# nixie_test_v4.net
KiCad netlist of a schematic drawn in EAGLE
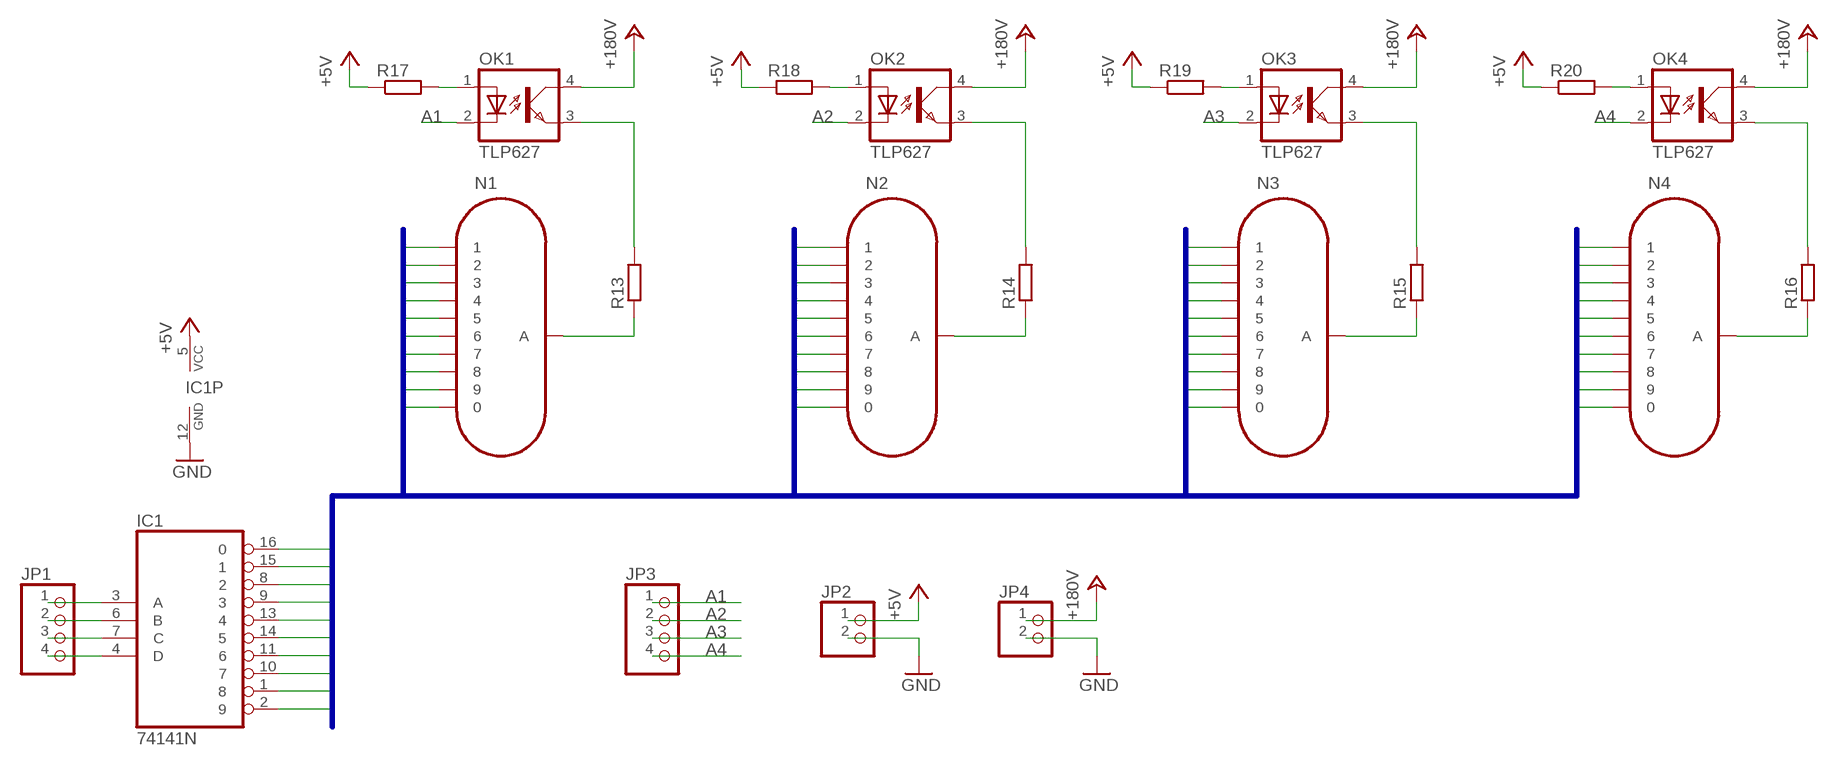
[diagram p0: schematic, sheet 1]

(export (version "E")
  (design (tool "Eeschema 10.0.6"))
  (components
    (comp (ref "IC1")
      (value "74141N")
      (footprint "eagle-import:DIL16")
      (libsource (lib "eagle-import") (part "74141N"))
    )
    (comp (ref "JP1")
      (value "PINHD-1X4")
      (footprint "eagle-import:1X04")
      (libsource (lib "eagle-import") (part "PINHD-1X4"))
    )
    (comp (ref "JP2")
      (value "PINHD-1X2")
      (footprint "eagle-import:1X02")
      (libsource (lib "eagle-import") (part "PINHD-1X2"))
    )
    (comp (ref "JP3")
      (value "PINHD-1X4")
      (footprint "eagle-import:1X04")
      (libsource (lib "eagle-import") (part "PINHD-1X4"))
    )
    (comp (ref "JP4")
      (value "PINHD-1X2")
      (footprint "eagle-import:1X02")
      (libsource (lib "eagle-import") (part "PINHD-1X2"))
    )
    (comp (ref "N1")
      (value "IN-17")
      (footprint "eagle-import:IN-17")
      (libsource (lib "eagle-import") (part "IN-17"))
    )
    (comp (ref "N2")
      (value "IN-17")
      (footprint "eagle-import:IN-17")
      (libsource (lib "eagle-import") (part "IN-17"))
    )
    (comp (ref "N3")
      (value "IN-17")
      (footprint "eagle-import:IN-17")
      (libsource (lib "eagle-import") (part "IN-17"))
    )
    (comp (ref "N4")
      (value "IN-17")
      (footprint "eagle-import:IN-17")
      (libsource (lib "eagle-import") (part "IN-17"))
    )
    (comp (ref "OK1")
      (value "TLP627")
      (footprint "eagle-import:4-SMD")
      (libsource (lib "eagle-import") (part "TLP627"))
    )
    (comp (ref "OK2")
      (value "TLP627")
      (footprint "eagle-import:4-SMD")
      (libsource (lib "eagle-import") (part "TLP627"))
    )
    (comp (ref "OK3")
      (value "TLP627")
      (footprint "eagle-import:4-SMD")
      (libsource (lib "eagle-import") (part "TLP627"))
    )
    (comp (ref "OK4")
      (value "TLP627")
      (footprint "eagle-import:4-SMD")
      (libsource (lib "eagle-import") (part "TLP627"))
    )
    (comp (ref "R13")
      (value "R-EU_10")
      (footprint "eagle-import:0207_10")
      (libsource (lib "eagle-import") (part "R-EU_10"))
    )
    (comp (ref "R14")
      (value "R-EU_10")
      (footprint "eagle-import:0207_10")
      (libsource (lib "eagle-import") (part "R-EU_10"))
    )
    (comp (ref "R15")
      (value "R-EU_10")
      (footprint "eagle-import:0207_10")
      (libsource (lib "eagle-import") (part "R-EU_10"))
    )
    (comp (ref "R16")
      (value "R-EU_10")
      (footprint "eagle-import:0207_10")
      (libsource (lib "eagle-import") (part "R-EU_10"))
    )
    (comp (ref "R17")
      (value "R-EU_R0805")
      (footprint "eagle-import:R0805")
      (libsource (lib "eagle-import") (part "R-EU_R0805"))
    )
    (comp (ref "R18")
      (value "R-EU_R0805")
      (footprint "eagle-import:R0805")
      (libsource (lib "eagle-import") (part "R-EU_R0805"))
    )
    (comp (ref "R19")
      (value "R-EU_R0805")
      (footprint "eagle-import:R0805")
      (libsource (lib "eagle-import") (part "R-EU_R0805"))
    )
    (comp (ref "R20")
      (value "R-EU_R0805")
      (footprint "eagle-import:R0805")
      (libsource (lib "eagle-import") (part "R-EU_R0805"))
    )
  )
  (nets
    (net (code "1") (name "+5V") (class "Default")
      (node (ref "IC1") (pin "5") (pinfunction "VCC_5") (pintype "power_in"))
      (node (ref "JP2") (pin "1") (pinfunction "1_1") (pintype "passive"))
      (node (ref "R17") (pin "1") (pinfunction "1_1") (pintype "passive"))
      (node (ref "R18") (pin "1") (pinfunction "1_1") (pintype "passive"))
      (node (ref "R19") (pin "1") (pinfunction "1_1") (pintype "passive"))
      (node (ref "R20") (pin "1") (pinfunction "1_1") (pintype "passive"))
    )
    (net (code "2") (name "+180V") (class "Default")
      (node (ref "JP4") (pin "1") (pinfunction "1_1") (pintype "passive"))
      (node (ref "OK1") (pin "4") (pinfunction "COL_4") (pintype "passive"))
      (node (ref "OK2") (pin "4") (pinfunction "COL_4") (pintype "passive"))
      (node (ref "OK3") (pin "4") (pinfunction "COL_4") (pintype "passive"))
      (node (ref "OK4") (pin "4") (pinfunction "COL_4") (pintype "passive"))
    )
    (net (code "3") (name "/A1") (class "Default")
      (node (ref "JP3") (pin "1") (pinfunction "1_1") (pintype "passive"))
      (node (ref "OK1") (pin "2") (pinfunction "C_2") (pintype "passive"))
    )
    (net (code "4") (name "/A2") (class "Default")
      (node (ref "JP3") (pin "2") (pinfunction "2_2") (pintype "passive"))
      (node (ref "OK2") (pin "2") (pinfunction "C_2") (pintype "passive"))
    )
    (net (code "5") (name "/A3") (class "Default")
      (node (ref "JP3") (pin "3") (pinfunction "3_3") (pintype "passive"))
      (node (ref "OK3") (pin "2") (pinfunction "C_2") (pintype "passive"))
    )
    (net (code "6") (name "/A4") (class "Default")
      (node (ref "JP3") (pin "4") (pinfunction "4_4") (pintype "passive"))
      (node (ref "OK4") (pin "2") (pinfunction "C_2") (pintype "passive"))
    )
    (net (code "7") (name "/C0") (class "Default")
      (node (ref "IC1") (pin "16") (pinfunction "0_16") (pintype "open_collector"))
      (node (ref "N1") (pin "0") (pinfunction "0_0") (pintype "bidirectional"))
      (node (ref "N2") (pin "0") (pinfunction "0_0") (pintype "bidirectional"))
      (node (ref "N3") (pin "0") (pinfunction "0_0") (pintype "bidirectional"))
      (node (ref "N4") (pin "0") (pinfunction "0_0") (pintype "bidirectional"))
    )
    (net (code "8") (name "/C1") (class "Default")
      (node (ref "IC1") (pin "15") (pinfunction "1_15") (pintype "open_collector"))
      (node (ref "N1") (pin "1") (pinfunction "1_1") (pintype "bidirectional"))
      (node (ref "N2") (pin "1") (pinfunction "1_1") (pintype "bidirectional"))
      (node (ref "N3") (pin "1") (pinfunction "1_1") (pintype "bidirectional"))
      (node (ref "N4") (pin "1") (pinfunction "1_1") (pintype "bidirectional"))
    )
    (net (code "9") (name "/C2") (class "Default")
      (node (ref "IC1") (pin "8") (pinfunction "2_8") (pintype "open_collector"))
      (node (ref "N1") (pin "2") (pinfunction "2_2") (pintype "bidirectional"))
      (node (ref "N2") (pin "2") (pinfunction "2_2") (pintype "bidirectional"))
      (node (ref "N3") (pin "2") (pinfunction "2_2") (pintype "bidirectional"))
      (node (ref "N4") (pin "2") (pinfunction "2_2") (pintype "bidirectional"))
    )
    (net (code "10") (name "/C3") (class "Default")
      (node (ref "IC1") (pin "9") (pinfunction "3_9") (pintype "open_collector"))
      (node (ref "N1") (pin "3") (pinfunction "3_3") (pintype "bidirectional"))
      (node (ref "N2") (pin "3") (pinfunction "3_3") (pintype "bidirectional"))
      (node (ref "N3") (pin "3") (pinfunction "3_3") (pintype "bidirectional"))
      (node (ref "N4") (pin "3") (pinfunction "3_3") (pintype "bidirectional"))
    )
    (net (code "11") (name "/C4") (class "Default")
      (node (ref "IC1") (pin "13") (pinfunction "4_13") (pintype "open_collector"))
      (node (ref "N1") (pin "4") (pinfunction "4_4") (pintype "bidirectional"))
      (node (ref "N2") (pin "4") (pinfunction "4_4") (pintype "bidirectional"))
      (node (ref "N3") (pin "4") (pinfunction "4_4") (pintype "bidirectional"))
      (node (ref "N4") (pin "4") (pinfunction "4_4") (pintype "bidirectional"))
    )
    (net (code "12") (name "/C5") (class "Default")
      (node (ref "IC1") (pin "14") (pinfunction "5_14") (pintype "open_collector"))
      (node (ref "N1") (pin "5") (pinfunction "5_5") (pintype "bidirectional"))
      (node (ref "N2") (pin "5") (pinfunction "5_5") (pintype "bidirectional"))
      (node (ref "N3") (pin "5") (pinfunction "5_5") (pintype "bidirectional"))
      (node (ref "N4") (pin "5") (pinfunction "5_5") (pintype "bidirectional"))
    )
    (net (code "13") (name "/C6") (class "Default")
      (node (ref "IC1") (pin "11") (pinfunction "6_11") (pintype "open_collector"))
      (node (ref "N1") (pin "6") (pinfunction "6_6") (pintype "bidirectional"))
      (node (ref "N2") (pin "6") (pinfunction "6_6") (pintype "bidirectional"))
      (node (ref "N3") (pin "6") (pinfunction "6_6") (pintype "bidirectional"))
      (node (ref "N4") (pin "6") (pinfunction "6_6") (pintype "bidirectional"))
    )
    (net (code "14") (name "/C7") (class "Default")
      (node (ref "IC1") (pin "10") (pinfunction "7_10") (pintype "open_collector"))
      (node (ref "N1") (pin "7") (pinfunction "7_7") (pintype "bidirectional"))
      (node (ref "N2") (pin "7") (pinfunction "7_7") (pintype "bidirectional"))
      (node (ref "N3") (pin "7") (pinfunction "7_7") (pintype "bidirectional"))
      (node (ref "N4") (pin "7") (pinfunction "7_7") (pintype "bidirectional"))
    )
    (net (code "15") (name "/C8") (class "Default")
      (node (ref "IC1") (pin "1") (pinfunction "8_1") (pintype "open_collector"))
      (node (ref "N1") (pin "8") (pinfunction "8_8") (pintype "bidirectional"))
      (node (ref "N2") (pin "8") (pinfunction "8_8") (pintype "bidirectional"))
      (node (ref "N3") (pin "8") (pinfunction "8_8") (pintype "bidirectional"))
      (node (ref "N4") (pin "8") (pinfunction "8_8") (pintype "bidirectional"))
    )
    (net (code "16") (name "/C9") (class "Default")
      (node (ref "IC1") (pin "2") (pinfunction "9_2") (pintype "open_collector"))
      (node (ref "N1") (pin "9") (pinfunction "9_9") (pintype "bidirectional"))
      (node (ref "N2") (pin "9") (pinfunction "9_9") (pintype "bidirectional"))
      (node (ref "N3") (pin "9") (pinfunction "9_9") (pintype "bidirectional"))
      (node (ref "N4") (pin "9") (pinfunction "9_9") (pintype "bidirectional"))
    )
    (net (code "17") (name "GND") (class "Default")
      (node (ref "IC1") (pin "12") (pinfunction "GND_12") (pintype "power_in"))
      (node (ref "JP2") (pin "2") (pinfunction "2_2") (pintype "passive"))
      (node (ref "JP4") (pin "2") (pinfunction "2_2") (pintype "passive"))
    )
    (net (code "18") (name "Net-(IC1A-A)") (class "Default")
      (node (ref "IC1") (pin "3") (pinfunction "A_3") (pintype "input"))
      (node (ref "JP1") (pin "1") (pinfunction "1_1") (pintype "passive"))
    )
    (net (code "19") (name "Net-(IC1A-B)") (class "Default")
      (node (ref "IC1") (pin "6") (pinfunction "B_6") (pintype "input"))
      (node (ref "JP1") (pin "2") (pinfunction "2_2") (pintype "passive"))
    )
    (net (code "20") (name "Net-(IC1A-C)") (class "Default")
      (node (ref "IC1") (pin "7") (pinfunction "C_7") (pintype "input"))
      (node (ref "JP1") (pin "3") (pinfunction "3_3") (pintype "passive"))
    )
    (net (code "21") (name "Net-(IC1A-D)") (class "Default")
      (node (ref "IC1") (pin "4") (pinfunction "D_4") (pintype "input"))
      (node (ref "JP1") (pin "4") (pinfunction "4_4") (pintype "passive"))
    )
    (net (code "22") (name "Net-(N1-PadA)") (class "Default")
      (node (ref "N1") (pin "A") (pinfunction "A_A") (pintype "bidirectional"))
      (node (ref "R13") (pin "1") (pinfunction "1_1") (pintype "passive"))
    )
    (net (code "23") (name "Net-(N2-PadA)") (class "Default")
      (node (ref "N2") (pin "A") (pinfunction "A_A") (pintype "bidirectional"))
      (node (ref "R14") (pin "1") (pinfunction "1_1") (pintype "passive"))
    )
    (net (code "24") (name "Net-(N3-PadA)") (class "Default")
      (node (ref "N3") (pin "A") (pinfunction "A_A") (pintype "bidirectional"))
      (node (ref "R15") (pin "1") (pinfunction "1_1") (pintype "passive"))
    )
    (net (code "25") (name "Net-(N4-PadA)") (class "Default")
      (node (ref "N4") (pin "A") (pinfunction "A_A") (pintype "bidirectional"))
      (node (ref "R16") (pin "1") (pinfunction "1_1") (pintype "passive"))
    )
    (net (code "26") (name "Net-(OK1-A)") (class "Default")
      (node (ref "OK1") (pin "1") (pinfunction "A_1") (pintype "passive"))
      (node (ref "R17") (pin "2") (pinfunction "2_2") (pintype "passive"))
    )
    (net (code "27") (name "Net-(OK1-EMIT)") (class "Default")
      (node (ref "OK1") (pin "3") (pinfunction "EMIT_3") (pintype "passive"))
      (node (ref "R13") (pin "2") (pinfunction "2_2") (pintype "passive"))
    )
    (net (code "28") (name "Net-(OK2-A)") (class "Default")
      (node (ref "OK2") (pin "1") (pinfunction "A_1") (pintype "passive"))
      (node (ref "R18") (pin "2") (pinfunction "2_2") (pintype "passive"))
    )
    (net (code "29") (name "Net-(OK2-EMIT)") (class "Default")
      (node (ref "OK2") (pin "3") (pinfunction "EMIT_3") (pintype "passive"))
      (node (ref "R14") (pin "2") (pinfunction "2_2") (pintype "passive"))
    )
    (net (code "30") (name "Net-(OK3-A)") (class "Default")
      (node (ref "OK3") (pin "1") (pinfunction "A_1") (pintype "passive"))
      (node (ref "R19") (pin "2") (pinfunction "2_2") (pintype "passive"))
    )
    (net (code "31") (name "Net-(OK3-EMIT)") (class "Default")
      (node (ref "OK3") (pin "3") (pinfunction "EMIT_3") (pintype "passive"))
      (node (ref "R15") (pin "2") (pinfunction "2_2") (pintype "passive"))
    )
    (net (code "32") (name "Net-(OK4-A)") (class "Default")
      (node (ref "OK4") (pin "1") (pinfunction "A_1") (pintype "passive"))
      (node (ref "R20") (pin "2") (pinfunction "2_2") (pintype "passive"))
    )
    (net (code "33") (name "Net-(OK4-EMIT)") (class "Default")
      (node (ref "OK4") (pin "3") (pinfunction "EMIT_3") (pintype "passive"))
      (node (ref "R16") (pin "2") (pinfunction "2_2") (pintype "passive"))
    )
  )
)
